# Peripherals.net
KiCad netlist of a schematic drawn in Altium Designer
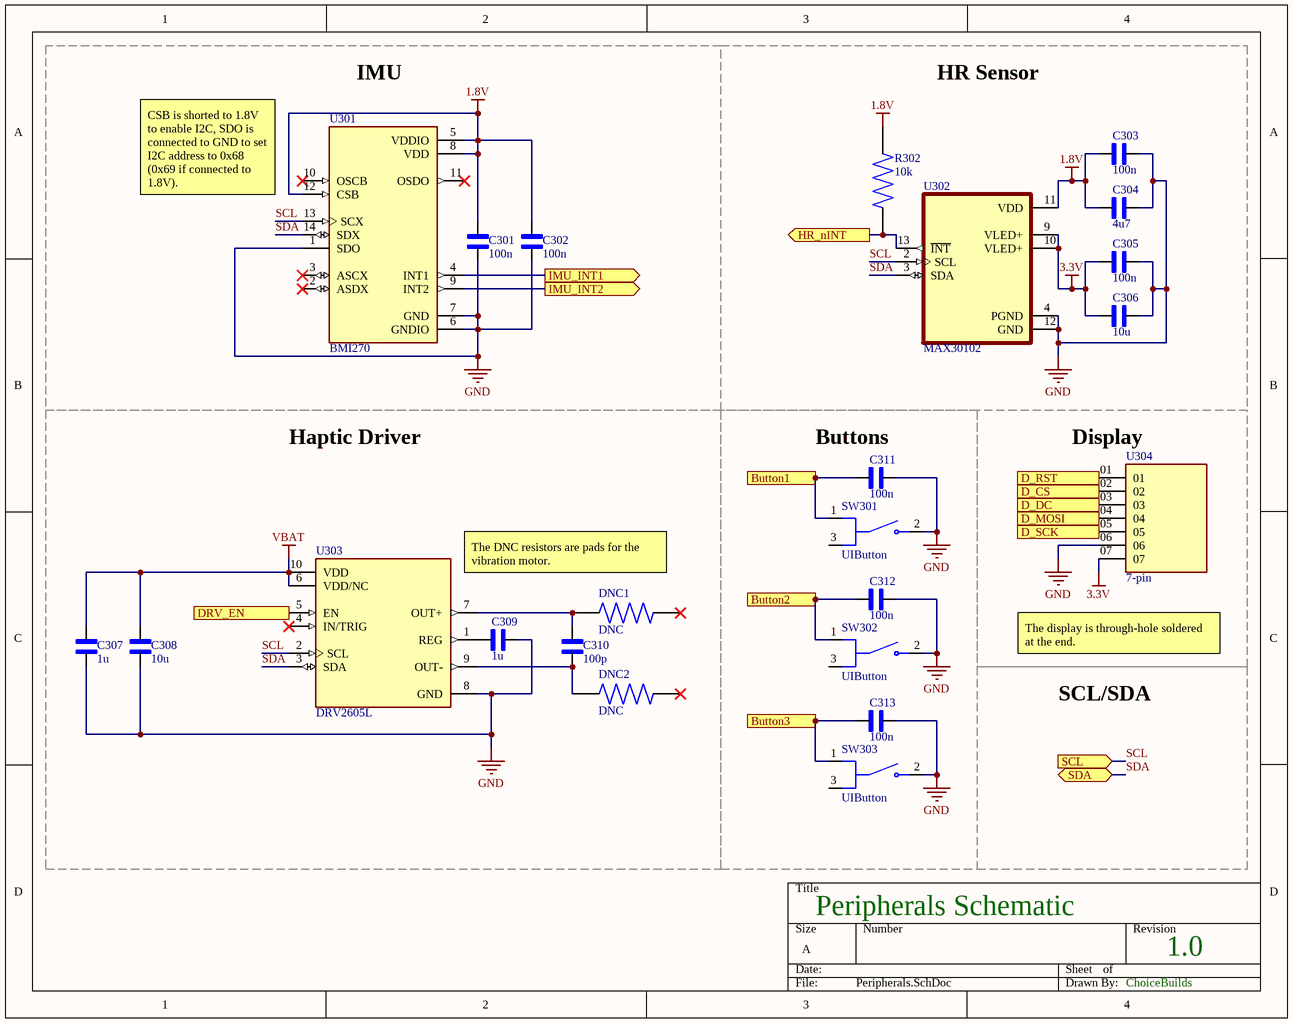
[diagram p0: Peripherals.SchDoc]

(export (version "E")
  (design (tool "Eeschema 10.0.6"))
  (components
    (comp (ref "C301") (value "100n") (footprint "0402c") (libsource (lib "") (part "0402c_2")))
    (comp (ref "C302") (value "100n") (footprint "0402c") (libsource (lib "") (part "0402c_2")))
    (comp (ref "C303") (value "100n") (footprint "0402c") (libsource (lib "UbiWatch_SchLib") (part "0402c")))
    (comp (ref "C304") (value "4u7") (footprint "0603c") (libsource (lib "UbiWatch_SchLib") (part "0603c")))
    (comp (ref "C305") (value "100n") (footprint "0402c") (libsource (lib "UbiWatch_SchLib") (part "0402c")))
    (comp (ref "C306") (value "10u") (footprint "0603c") (libsource (lib "UbiWatch_SchLib") (part "0603c")))
    (comp (ref "C307") (value "1u") (footprint "0402c") (libsource (lib "") (part "0402c_2")))
    (comp (ref "C308") (value "10u") (footprint "0603c") (libsource (lib "") (part "0603c_1")))
    (comp (ref "C309") (value "1u") (footprint "0603c") (libsource (lib "") (part "0603c_2")))
    (comp (ref "C310") (value "100p") (footprint "0402c") (libsource (lib "") (part "0402c_2")))
    (comp (ref "C311") (value "100n") (footprint "0402c") (libsource (lib "") (part "0402c_1")))
    (comp (ref "C312") (value "100n") (footprint "0402c") (libsource (lib "") (part "0402c_1")))
    (comp (ref "C313") (value "100n") (footprint "0402c") (libsource (lib "") (part "0402c_1")))
    (comp (ref "DNC1") (value "DNC") (footprint "0805r") (libsource (lib "UbiWatch_SchLib") (part "0805r")))
    (comp (ref "DNC2") (value "DNC") (footprint "0805r") (libsource (lib "UbiWatch_SchLib") (part "0805r")))
    (comp (ref "R302") (value "10k") (footprint "0402r") (libsource (lib "UbiWatch_SchLib") (part "0402r")))
    (comp (ref "SW301")
      (value "UIButton")
      (footprint "TL3340AF160QG")
      (libsource (lib "JWatch_SchLib") (part "TL3340AF160QG"))
    )
    (comp (ref "SW302")
      (value "UIButton")
      (footprint "TL3340AF160QG")
      (libsource (lib "JWatch_SchLib") (part "TL3340AF160QG"))
    )
    (comp (ref "SW303")
      (value "UIButton")
      (footprint "TL3340AF160QG")
      (libsource (lib "JWatch_SchLib") (part "TL3340AF160QG"))
    )
    (comp (ref "U301")
      (value "BMI270")
      (footprint "BMI270")
      (libsource (lib "JWatch_SchLib") (part "BMI270"))
    )
    (comp (ref "U302")
      (value "MAX30102")
      (footprint "MAX30102")
      (libsource (lib "JWatch_SchLib") (part "MAX30102"))
    )
    (comp (ref "U303")
      (value "DRV2605L")
      (footprint "DRV2605L")
      (libsource (lib "JWatch_SchLib") (part "DRV2605L"))
    )
    (comp (ref "U304") (value "7-pin") (footprint "7-pin") (libsource (lib "UbiWatch_SchLib") (part "7-pin")))
  )
  (nets
    (net (code "1") (name "/Button1") (class "Default")
      (node (ref "C311") (pin "1") (pinfunction "1_1") (pintype "passive"))
      (node (ref "SW301") (pin "1") (pinfunction "COM_1_1") (pintype "passive"))
    )
    (net (code "2") (name "/Button2") (class "Default")
      (node (ref "C312") (pin "1") (pinfunction "1_1") (pintype "passive"))
      (node (ref "SW302") (pin "1") (pinfunction "COM_1_1") (pintype "passive"))
    )
    (net (code "3") (name "/Button3") (class "Default")
      (node (ref "C313") (pin "1") (pinfunction "1_1") (pintype "passive"))
      (node (ref "SW303") (pin "1") (pinfunction "COM_1_1") (pintype "passive"))
    )
    (net (code "4") (name "/DRV_EN") (class "Default")
      (node (ref "U303") (pin "5") (pinfunction "EN_5") (pintype "input"))
    )
    (net (code "5") (name "/D_CS") (class "Default")
      (node (ref "U304") (pin "02") (pinfunction "02_02") (pintype "passive"))
    )
    (net (code "6") (name "/D_DC") (class "Default")
      (node (ref "U304") (pin "03") (pinfunction "03_03") (pintype "passive"))
    )
    (net (code "7") (name "/D_MOSI") (class "Default")
      (node (ref "U304") (pin "04") (pinfunction "04_04") (pintype "passive"))
    )
    (net (code "8") (name "/D_RST") (class "Default")
      (node (ref "U304") (pin "01") (pinfunction "01_01") (pintype "passive"))
    )
    (net (code "9") (name "/D_SCK") (class "Default")
      (node (ref "U304") (pin "05") (pinfunction "05_05") (pintype "passive"))
    )
    (net (code "10") (name "/HR_nINT") (class "Default")
      (node (ref "R302") (pin "1") (pinfunction "1_1") (pintype "passive"))
      (node (ref "U302") (pin "13") (pinfunction "~{INT}_13") (pintype "output"))
    )
    (net (code "11") (name "/IMU_INT1") (class "Default")
      (node (ref "U301") (pin "4") (pinfunction "INT1_4") (pintype "output"))
    )
    (net (code "12") (name "/IMU_INT2") (class "Default")
      (node (ref "U301") (pin "9") (pinfunction "INT2_9") (pintype "output"))
    )
    (net (code "13") (name "/SCL") (class "Default")
      (node (ref "U301") (pin "13") (pinfunction "SCX_13") (pintype "input"))
      (node (ref "U302") (pin "2") (pinfunction "SCL_2") (pintype "input"))
      (node (ref "U303") (pin "2") (pinfunction "SCL_2") (pintype "input"))
    )
    (net (code "14") (name "/SDA") (class "Default")
      (node (ref "U301") (pin "14") (pinfunction "SDX_14") (pintype "bidirectional"))
      (node (ref "U302") (pin "3") (pinfunction "SDA_3") (pintype "bidirectional"))
      (node (ref "U303") (pin "3") (pinfunction "SDA_3") (pintype "bidirectional"))
    )
    (net (code "15") (name "1.8V") (class "Default")
      (node (ref "C301") (pin "2") (pinfunction "2_2") (pintype "passive"))
      (node (ref "C302") (pin "2") (pinfunction "2_2") (pintype "passive"))
      (node (ref "C303") (pin "2") (pinfunction "2_2") (pintype "passive"))
      (node (ref "C304") (pin "2") (pinfunction "2_2") (pintype "passive"))
      (node (ref "R302") (pin "2") (pinfunction "2_2") (pintype "passive"))
      (node (ref "U301") (pin "12") (pinfunction "CSB_12") (pintype "input"))
      (node (ref "U301") (pin "5") (pinfunction "VDDIO_5") (pintype "power_in"))
      (node (ref "U301") (pin "8") (pinfunction "VDD_8") (pintype "power_in"))
      (node (ref "U302") (pin "11") (pinfunction "VDD_11") (pintype "power_in"))
    )
    (net (code "16") (name "3.3V") (class "Default")
      (node (ref "C305") (pin "2") (pinfunction "2_2") (pintype "passive"))
      (node (ref "C306") (pin "2") (pinfunction "2_2") (pintype "passive"))
      (node (ref "U302") (pin "10") (pinfunction "VLED+_10") (pintype "power_in"))
      (node (ref "U302") (pin "9") (pinfunction "VLED+_9") (pintype "power_in"))
      (node (ref "U304") (pin "07") (pinfunction "07_07") (pintype "passive"))
    )
    (net (code "17") (name "GND") (class "Default")
      (node (ref "C301") (pin "1") (pinfunction "1_1") (pintype "passive"))
      (node (ref "C302") (pin "1") (pinfunction "1_1") (pintype "passive"))
      (node (ref "C303") (pin "1") (pinfunction "1_1") (pintype "passive"))
      (node (ref "C304") (pin "1") (pinfunction "1_1") (pintype "passive"))
      (node (ref "C305") (pin "1") (pinfunction "1_1") (pintype "passive"))
      (node (ref "C306") (pin "1") (pinfunction "1_1") (pintype "passive"))
      (node (ref "C307") (pin "1") (pinfunction "1_1") (pintype "passive"))
      (node (ref "C308") (pin "1") (pinfunction "1_1") (pintype "passive"))
      (node (ref "C309") (pin "2") (pinfunction "2_2") (pintype "passive"))
      (node (ref "C311") (pin "2") (pinfunction "2_2") (pintype "passive"))
      (node (ref "C312") (pin "2") (pinfunction "2_2") (pintype "passive"))
      (node (ref "C313") (pin "2") (pinfunction "2_2") (pintype "passive"))
      (node (ref "SW301") (pin "2") (pinfunction "NO_2") (pintype "passive"))
      (node (ref "SW302") (pin "2") (pinfunction "NO_2") (pintype "passive"))
      (node (ref "SW303") (pin "2") (pinfunction "NO_2") (pintype "passive"))
      (node (ref "U301") (pin "1") (pinfunction "SDO_1") (pintype "passive"))
      (node (ref "U301") (pin "6") (pinfunction "GNDIO_6") (pintype "power_in"))
      (node (ref "U301") (pin "7") (pinfunction "GND_7") (pintype "power_in"))
      (node (ref "U302") (pin "12") (pinfunction "GND_12") (pintype "power_in"))
      (node (ref "U302") (pin "4") (pinfunction "PGND_4") (pintype "power_in"))
      (node (ref "U303") (pin "8") (pinfunction "GND_8") (pintype "power_in"))
      (node (ref "U304") (pin "06") (pinfunction "06_06") (pintype "passive"))
    )
    (net (code "18") (name "Net-(U303-OUT+)") (class "Default")
      (node (ref "C310") (pin "2") (pinfunction "2_2") (pintype "passive"))
      (node (ref "DNC1") (pin "1") (pinfunction "1_1") (pintype "passive"))
      (node (ref "U303") (pin "7") (pinfunction "OUT+_7") (pintype "output"))
    )
    (net (code "19") (name "Net-(U303-OUT-)") (class "Default")
      (node (ref "C310") (pin "1") (pinfunction "1_1") (pintype "passive"))
      (node (ref "DNC2") (pin "1") (pinfunction "1_1") (pintype "passive"))
      (node (ref "U303") (pin "9") (pinfunction "OUT-_9") (pintype "output"))
    )
    (net (code "20") (name "Net-(U303-REG)") (class "Default")
      (node (ref "C309") (pin "1") (pinfunction "1_1") (pintype "passive"))
      (node (ref "U303") (pin "1") (pinfunction "REG_1") (pintype "output"))
    )
    (net (code "21") (name "VBAT") (class "Default")
      (node (ref "C307") (pin "2") (pinfunction "2_2") (pintype "passive"))
      (node (ref "C308") (pin "2") (pinfunction "2_2") (pintype "passive"))
      (node (ref "U303") (pin "10") (pinfunction "VDD_10") (pintype "power_in"))
      (node (ref "U303") (pin "6") (pinfunction "VDD/NC_6") (pintype "power_in"))
    )
    (net (code "22") (name "unconnected-(DNC1-Pad2)") (class "Default")
      (node (ref "DNC1") (pin "2") (pinfunction "2_2") (pintype "passive+no_connect"))
    )
    (net (code "23") (name "unconnected-(DNC2-Pad2)") (class "Default")
      (node (ref "DNC2") (pin "2") (pinfunction "2_2") (pintype "passive+no_connect"))
    )
    (net (code "24") (name "unconnected-(SW301-COM_2-Pad3)") (class "Default")
      (node (ref "SW301") (pin "3") (pinfunction "COM_2_3") (pintype "passive"))
    )
    (net (code "25") (name "unconnected-(SW302-COM_2-Pad3)") (class "Default")
      (node (ref "SW302") (pin "3") (pinfunction "COM_2_3") (pintype "passive"))
    )
    (net (code "26") (name "unconnected-(SW303-COM_2-Pad3)") (class "Default")
      (node (ref "SW303") (pin "3") (pinfunction "COM_2_3") (pintype "passive"))
    )
    (net (code "27") (name "unconnected-(U301-ASCX-Pad3)") (class "Default")
      (node (ref "U301") (pin "3") (pinfunction "ASCX_3") (pintype "bidirectional+no_connect"))
    )
    (net (code "28") (name "unconnected-(U301-ASDX-Pad2)") (class "Default")
      (node (ref "U301") (pin "2") (pinfunction "ASDX_2") (pintype "bidirectional+no_connect"))
    )
    (net (code "29") (name "unconnected-(U301-OSCB-Pad10)") (class "Default")
      (node (ref "U301") (pin "10") (pinfunction "OSCB_10") (pintype "input+no_connect"))
    )
    (net (code "30") (name "unconnected-(U301-OSDO-Pad11)") (class "Default")
      (node (ref "U301") (pin "11") (pinfunction "OSDO_11") (pintype "output+no_connect"))
    )
    (net (code "31") (name "unconnected-(U303-IN{slash}TRIG-Pad4)") (class "Default")
      (node (ref "U303") (pin "4") (pinfunction "IN/TRIG_4") (pintype "input+no_connect"))
    )
  )
)
